# pcb-inductive-sensor.net
KiCad netlist of a schematic drawn in EAGLE
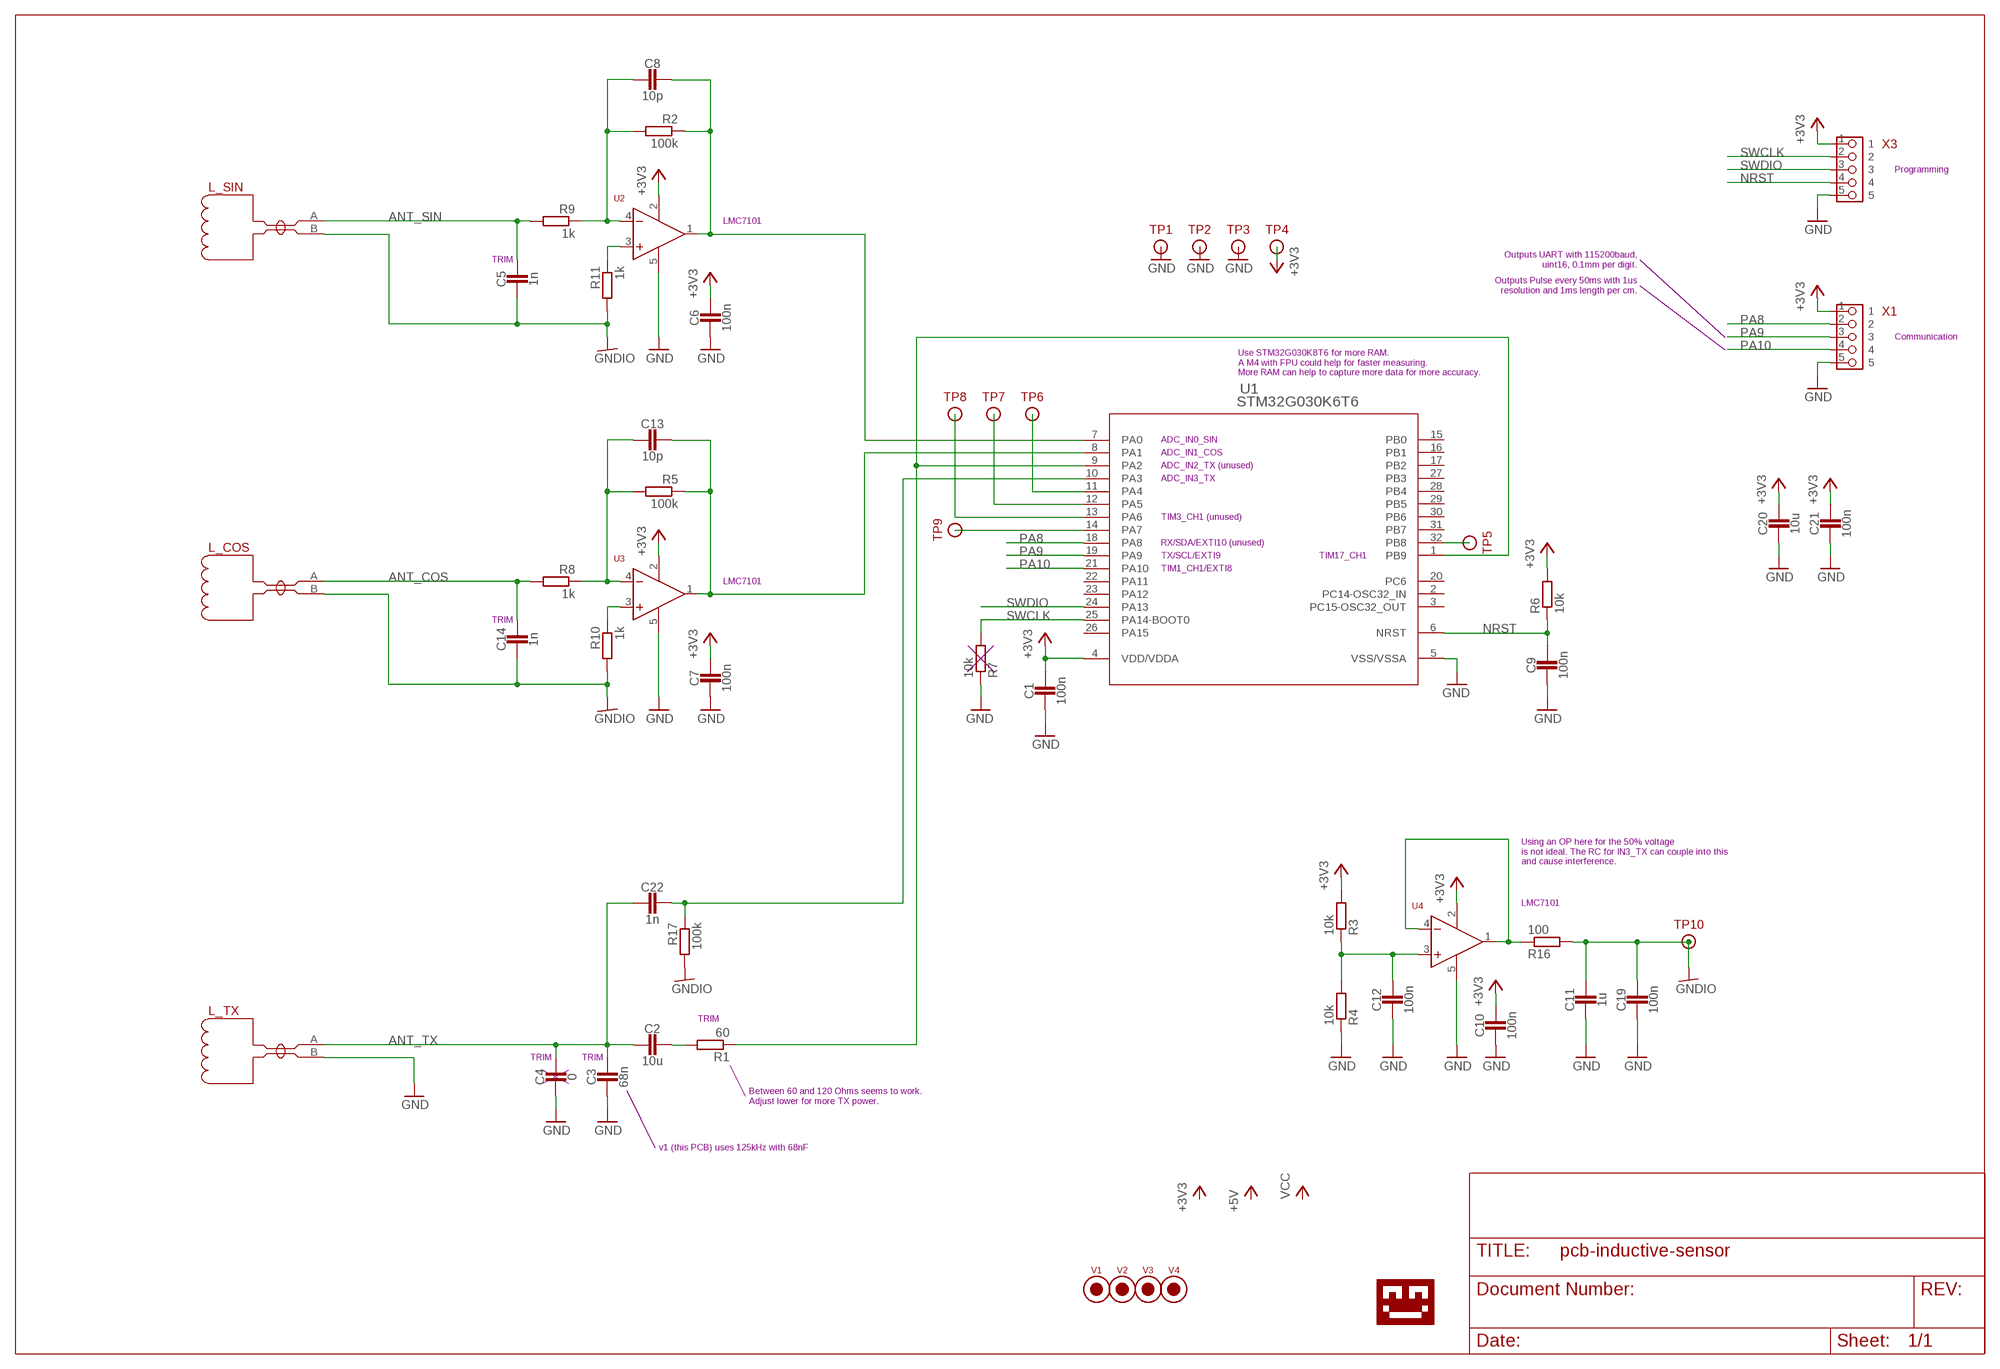
[diagram p0: schematic, sheet 1]

(export (version "E")
  (design (tool "Eeschema 10.0.6"))
  (components
    (comp (ref "C1")
      (value "100n")
      (footprint "eagle-import:0603_CAP")
      (libsource (lib "eagle-import") (part "CAPACITOR0603_CAP"))
    )
    (comp (ref "C2")
      (value "10u")
      (footprint "eagle-import:0805_CAP")
      (libsource (lib "eagle-import") (part "CAPACITOR0805_CAP"))
    )
    (comp (ref "C3")
      (value "68n")
      (footprint "eagle-import:0603_CAP")
      (libsource (lib "eagle-import") (part "CAPACITOR0603_CAP"))
    )
    (comp (ref "C4")
      (value "0")
      (footprint "eagle-import:0603_CAP")
      (libsource (lib "eagle-import") (part "CAPACITOR0603_CAP"))
    )
    (comp (ref "C5")
      (value "1n")
      (footprint "eagle-import:0603_CAP")
      (libsource (lib "eagle-import") (part "CAPACITOR0603_CAP"))
    )
    (comp (ref "C6")
      (value "100n")
      (footprint "eagle-import:0603_CAP")
      (libsource (lib "eagle-import") (part "CAPACITOR0603_CAP"))
    )
    (comp (ref "C7")
      (value "100n")
      (footprint "eagle-import:0603_CAP")
      (libsource (lib "eagle-import") (part "CAPACITOR0603_CAP"))
    )
    (comp (ref "C8")
      (value "10p")
      (footprint "eagle-import:0603_CAP")
      (libsource (lib "eagle-import") (part "CAPACITOR0603_CAP"))
    )
    (comp (ref "C9")
      (value "100n")
      (footprint "eagle-import:0603_CAP")
      (libsource (lib "eagle-import") (part "CAPACITOR0603_CAP"))
    )
    (comp (ref "C10")
      (value "100n")
      (footprint "eagle-import:0603_CAP")
      (libsource (lib "eagle-import") (part "CAPACITOR0603_CAP"))
    )
    (comp (ref "C11")
      (value "1u")
      (footprint "eagle-import:0603_CAP")
      (libsource (lib "eagle-import") (part "CAPACITOR0603_CAP"))
    )
    (comp (ref "C12")
      (value "100n")
      (footprint "eagle-import:0603_CAP")
      (libsource (lib "eagle-import") (part "CAPACITOR0603_CAP"))
    )
    (comp (ref "C13")
      (value "10p")
      (footprint "eagle-import:0603_CAP")
      (libsource (lib "eagle-import") (part "CAPACITOR0603_CAP"))
    )
    (comp (ref "C14")
      (value "1n")
      (footprint "eagle-import:0603_CAP")
      (libsource (lib "eagle-import") (part "CAPACITOR0603_CAP"))
    )
    (comp (ref "C19")
      (value "100n")
      (footprint "eagle-import:0603_CAP")
      (libsource (lib "eagle-import") (part "CAPACITOR0603_CAP"))
    )
    (comp (ref "C20")
      (value "10u")
      (footprint "eagle-import:0805_CAP")
      (libsource (lib "eagle-import") (part "CAPACITOR0805_CAP"))
    )
    (comp (ref "C21")
      (value "100n")
      (footprint "eagle-import:0603_CAP")
      (libsource (lib "eagle-import") (part "CAPACITOR0603_CAP"))
    )
    (comp (ref "C22")
      (value "1n")
      (footprint "eagle-import:0603_CAP")
      (libsource (lib "eagle-import") (part "CAPACITOR0603_CAP"))
    )
    (comp (ref "L_COS")
      (value "INDUCTION_SENSOR")
      (footprint "eagle-import:INDUCTIVE_SENSOR_NET_TIE")
      (libsource (lib "eagle-import") (part "INDUCTION_SENSOR"))
    )
    (comp (ref "L_SIN")
      (value "INDUCTION_SENSOR")
      (footprint "eagle-import:INDUCTIVE_SENSOR_NET_TIE")
      (libsource (lib "eagle-import") (part "INDUCTION_SENSOR"))
    )
    (comp (ref "L_TX")
      (value "INDUCTION_SENSOR")
      (footprint "eagle-import:INDUCTIVE_SENSOR_NET_TIE")
      (libsource (lib "eagle-import") (part "INDUCTION_SENSOR"))
    )
    (comp (ref "R1")
      (value "60")
      (footprint "eagle-import:0805_RES")
      (libsource (lib "eagle-import") (part "RESISTOR0805_RES"))
    )
    (comp (ref "R2")
      (value "100k")
      (footprint "eagle-import:0603-RES")
      (libsource (lib "eagle-import") (part "RESISTOR0603_RES"))
    )
    (comp (ref "R3")
      (value "10k")
      (footprint "eagle-import:0603-RES")
      (libsource (lib "eagle-import") (part "RESISTOR0603_RES"))
    )
    (comp (ref "R4")
      (value "10k")
      (footprint "eagle-import:0603-RES")
      (libsource (lib "eagle-import") (part "RESISTOR0603_RES"))
    )
    (comp (ref "R5")
      (value "100k")
      (footprint "eagle-import:0603-RES")
      (libsource (lib "eagle-import") (part "RESISTOR0603_RES"))
    )
    (comp (ref "R6")
      (value "10k")
      (footprint "eagle-import:0603-RES")
      (libsource (lib "eagle-import") (part "RESISTOR0603_RES"))
    )
    (comp (ref "R7")
      (value "10k")
      (footprint "eagle-import:0603-RES")
      (libsource (lib "eagle-import") (part "RESISTOR0603_RES"))
    )
    (comp (ref "R8")
      (value "1k")
      (footprint "eagle-import:0603-RES")
      (libsource (lib "eagle-import") (part "RESISTOR0603_RES"))
    )
    (comp (ref "R9")
      (value "1k")
      (footprint "eagle-import:0603-RES")
      (libsource (lib "eagle-import") (part "RESISTOR0603_RES"))
    )
    (comp (ref "R10")
      (value "1k")
      (footprint "eagle-import:0603-RES")
      (libsource (lib "eagle-import") (part "RESISTOR0603_RES"))
    )
    (comp (ref "R11")
      (value "1k")
      (footprint "eagle-import:0603-RES")
      (libsource (lib "eagle-import") (part "RESISTOR0603_RES"))
    )
    (comp (ref "R16")
      (value "100")
      (footprint "eagle-import:0603-RES")
      (libsource (lib "eagle-import") (part "RESISTOR0603_RES"))
    )
    (comp (ref "R17")
      (value "100k")
      (footprint "eagle-import:0603-RES")
      (libsource (lib "eagle-import") (part "RESISTOR0603_RES"))
    )
    (comp (ref "TP1")
      (value "TESTPIN")
      (footprint "eagle-import:PIN-SMD-1X1-TEST_1M5")
      (libsource (lib "eagle-import") (part "TESTPIN"))
    )
    (comp (ref "TP2")
      (value "TESTPIN")
      (footprint "eagle-import:PIN-SMD-1X1-TEST_1M5")
      (libsource (lib "eagle-import") (part "TESTPIN"))
    )
    (comp (ref "TP3")
      (value "TESTPIN")
      (footprint "eagle-import:PIN-SMD-1X1-TEST_1M5")
      (libsource (lib "eagle-import") (part "TESTPIN"))
    )
    (comp (ref "TP4")
      (value "TESTPIN")
      (footprint "eagle-import:PIN-SMD-1X1-TEST_1M5")
      (libsource (lib "eagle-import") (part "TESTPIN"))
    )
    (comp (ref "TP5")
      (value "TESTPIN")
      (footprint "eagle-import:PIN-SMD-1X1-TEST_1M5")
      (libsource (lib "eagle-import") (part "TESTPIN"))
    )
    (comp (ref "TP6")
      (value "TESTPIN")
      (footprint "eagle-import:PIN-SMD-1X1-TEST_1M5")
      (libsource (lib "eagle-import") (part "TESTPIN"))
    )
    (comp (ref "TP7")
      (value "TESTPIN")
      (footprint "eagle-import:PIN-SMD-1X1-TEST_1M5")
      (libsource (lib "eagle-import") (part "TESTPIN"))
    )
    (comp (ref "TP8")
      (value "TESTPIN")
      (footprint "eagle-import:PIN-SMD-1X1-TEST_1M5")
      (libsource (lib "eagle-import") (part "TESTPIN"))
    )
    (comp (ref "TP9")
      (value "TESTPIN")
      (footprint "eagle-import:PIN-SMD-1X1-TEST_1M5")
      (libsource (lib "eagle-import") (part "TESTPIN"))
    )
    (comp (ref "TP10")
      (value "TESTPIN")
      (footprint "eagle-import:PIN-SMD-1X1-TEST_1M5")
      (libsource (lib "eagle-import") (part "TESTPIN"))
    )
    (comp (ref "U$1")
      (value "LOGO-TOBENG-1MM-FINISH")
      (footprint "eagle-import:TOBENG-1MM-FINISH")
      (libsource (lib "eagle-import") (part "LOGO-TOBENG-1MM-FINISH"))
    )
    (comp (ref "U1")
      (value "STM32G030K6T6")
      (footprint "eagle-import:LQFP-32")
      (fields (field (name "COPYRIGHT") "Copyright (C) 2018 Accelerated Designs. All rights reserved"))
      (libsource (lib "eagle-import") (part "STM32G030K6T6"))
    )
    (comp (ref "U2")
      (value "OPAMP-LMC7101")
      (footprint "eagle-import:SOT-23-5")
      (libsource (lib "eagle-import") (part "OPAMP-LMC7101"))
    )
    (comp (ref "U3")
      (value "OPAMP-LMC7101")
      (footprint "eagle-import:SOT-23-5")
      (libsource (lib "eagle-import") (part "OPAMP-LMC7101"))
    )
    (comp (ref "U4")
      (value "OPAMP-LMC7101")
      (footprint "eagle-import:SOT-23-5")
      (libsource (lib "eagle-import") (part "OPAMP-LMC7101"))
    )
    (comp (ref "V1")
      (value "FIDUCIAL2MM")
      (footprint "eagle-import:FIDUCIAL_2MM")
      (libsource (lib "eagle-import") (part "FIDUCIAL2MM"))
    )
    (comp (ref "V2")
      (value "FIDUCIAL2MM")
      (footprint "eagle-import:FIDUCIAL_2MM")
      (libsource (lib "eagle-import") (part "FIDUCIAL2MM"))
    )
    (comp (ref "V3")
      (value "FIDUCIAL2MM")
      (footprint "eagle-import:FIDUCIAL_2MM")
      (libsource (lib "eagle-import") (part "FIDUCIAL2MM"))
    )
    (comp (ref "V4")
      (value "FIDUCIAL2MM")
      (footprint "eagle-import:FIDUCIAL_2MM")
      (libsource (lib "eagle-import") (part "FIDUCIAL2MM"))
    )
    (comp (ref "X1")
      (value "PIN_5X1HD")
      (footprint "eagle-import:PIN_5X1_HD")
      (libsource (lib "eagle-import") (part "PIN_5X1HD"))
    )
    (comp (ref "X3")
      (value "PIN_5X1HD")
      (footprint "eagle-import:PIN_5X1_HD")
      (libsource (lib "eagle-import") (part "PIN_5X1HD"))
    )
  )
  (nets
    (net (code "1") (name "+3V3") (class "Default")
      (node (ref "C1") (pin "1") (pinfunction "1_1") (pintype "bidirectional"))
      (node (ref "C10") (pin "1") (pinfunction "1_1") (pintype "bidirectional"))
      (node (ref "C20") (pin "P$1") (pinfunction "1_P$1") (pintype "bidirectional"))
      (node (ref "C21") (pin "1") (pinfunction "1_1") (pintype "bidirectional"))
      (node (ref "C6") (pin "1") (pinfunction "1_1") (pintype "bidirectional"))
      (node (ref "C7") (pin "1") (pinfunction "1_1") (pintype "bidirectional"))
      (node (ref "R3") (pin "2") (pinfunction "2_2") (pintype "passive"))
      (node (ref "R6") (pin "2") (pinfunction "2_2") (pintype "passive"))
      (node (ref "TP4") (pin "1") (pinfunction "1_1") (pintype "bidirectional"))
      (node (ref "U1") (pin "4") (pinfunction "VDD/VDDA_4") (pintype "power_in"))
      (node (ref "U2") (pin "2") (pinfunction "VCC_2") (pintype "bidirectional"))
      (node (ref "U3") (pin "2") (pinfunction "VCC_2") (pintype "bidirectional"))
      (node (ref "U4") (pin "2") (pinfunction "VCC_2") (pintype "bidirectional"))
      (node (ref "X1") (pin "1") (pinfunction "1_1") (pintype "bidirectional"))
      (node (ref "X3") (pin "1") (pinfunction "1_1") (pintype "bidirectional"))
    )
    (net (code "3") (name "/ANT_COS") (class "Default")
      (node (ref "C14") (pin "1") (pinfunction "1_1") (pintype "bidirectional"))
      (node (ref "L_COS") (pin "A") (pinfunction "A_A") (pintype "bidirectional"))
      (node (ref "R8") (pin "2") (pinfunction "2_2") (pintype "passive"))
    )
    (net (code "4") (name "/ANT_SIN") (class "Default")
      (node (ref "C5") (pin "1") (pinfunction "1_1") (pintype "bidirectional"))
      (node (ref "L_SIN") (pin "A") (pinfunction "A_A") (pintype "bidirectional"))
      (node (ref "R9") (pin "2") (pinfunction "2_2") (pintype "passive"))
    )
    (net (code "5") (name "/ANT_TX") (class "Default")
      (node (ref "C2") (pin "P$2") (pinfunction "2_P$2") (pintype "bidirectional"))
      (node (ref "C22") (pin "2") (pinfunction "2_2") (pintype "bidirectional"))
      (node (ref "C3") (pin "1") (pinfunction "1_1") (pintype "bidirectional"))
      (node (ref "C4") (pin "1") (pinfunction "1_1") (pintype "bidirectional"))
      (node (ref "L_TX") (pin "A") (pinfunction "A_A") (pintype "bidirectional"))
    )
    (net (code "6") (name "/NRST") (class "Default")
      (node (ref "C9") (pin "1") (pinfunction "1_1") (pintype "bidirectional"))
      (node (ref "R6") (pin "1") (pinfunction "1_1") (pintype "passive"))
      (node (ref "U1") (pin "6") (pinfunction "NRST_6") (pintype "bidirectional"))
      (node (ref "X3") (pin "4") (pinfunction "4_4") (pintype "bidirectional"))
    )
    (net (code "7") (name "/PA8") (class "Default")
      (node (ref "U1") (pin "18") (pinfunction "PA8_18") (pintype "bidirectional"))
      (node (ref "X1") (pin "2") (pinfunction "2_2") (pintype "bidirectional"))
    )
    (net (code "8") (name "/PA9") (class "Default")
      (node (ref "U1") (pin "19") (pinfunction "PA9_19") (pintype "bidirectional"))
      (node (ref "X1") (pin "3") (pinfunction "3_3") (pintype "bidirectional"))
    )
    (net (code "9") (name "/PA10") (class "Default")
      (node (ref "U1") (pin "21") (pinfunction "PA10_21") (pintype "bidirectional"))
      (node (ref "X1") (pin "4") (pinfunction "4_4") (pintype "bidirectional"))
    )
    (net (code "10") (name "/SWCLK") (class "Default")
      (node (ref "R7") (pin "2") (pinfunction "2_2") (pintype "passive"))
      (node (ref "U1") (pin "25") (pinfunction "PA14-BOOT0_25") (pintype "bidirectional"))
      (node (ref "X3") (pin "2") (pinfunction "2_2") (pintype "bidirectional"))
    )
    (net (code "11") (name "/SWDIO") (class "Default")
      (node (ref "U1") (pin "24") (pinfunction "PA13_24") (pintype "bidirectional"))
      (node (ref "X3") (pin "3") (pinfunction "3_3") (pintype "bidirectional"))
    )
    (net (code "12") (name "GND") (class "Default")
      (node (ref "C1") (pin "2") (pinfunction "2_2") (pintype "bidirectional"))
      (node (ref "C10") (pin "2") (pinfunction "2_2") (pintype "bidirectional"))
      (node (ref "C11") (pin "2") (pinfunction "2_2") (pintype "bidirectional"))
      (node (ref "C12") (pin "2") (pinfunction "2_2") (pintype "bidirectional"))
      (node (ref "C19") (pin "2") (pinfunction "2_2") (pintype "bidirectional"))
      (node (ref "C20") (pin "P$2") (pinfunction "2_P$2") (pintype "bidirectional"))
      (node (ref "C21") (pin "2") (pinfunction "2_2") (pintype "bidirectional"))
      (node (ref "C3") (pin "2") (pinfunction "2_2") (pintype "bidirectional"))
      (node (ref "C4") (pin "2") (pinfunction "2_2") (pintype "bidirectional"))
      (node (ref "C6") (pin "2") (pinfunction "2_2") (pintype "bidirectional"))
      (node (ref "C7") (pin "2") (pinfunction "2_2") (pintype "bidirectional"))
      (node (ref "C9") (pin "2") (pinfunction "2_2") (pintype "bidirectional"))
      (node (ref "L_TX") (pin "B") (pinfunction "B_B") (pintype "bidirectional"))
      (node (ref "R4") (pin "1") (pinfunction "1_1") (pintype "passive"))
      (node (ref "R7") (pin "1") (pinfunction "1_1") (pintype "passive"))
      (node (ref "TP1") (pin "1") (pinfunction "1_1") (pintype "bidirectional"))
      (node (ref "TP2") (pin "1") (pinfunction "1_1") (pintype "bidirectional"))
      (node (ref "TP3") (pin "1") (pinfunction "1_1") (pintype "bidirectional"))
      (node (ref "U1") (pin "5") (pinfunction "VSS/VSSA_5") (pintype "power_in"))
      (node (ref "U2") (pin "5") (pinfunction "GND_5") (pintype "bidirectional"))
      (node (ref "U3") (pin "5") (pinfunction "GND_5") (pintype "bidirectional"))
      (node (ref "U4") (pin "5") (pinfunction "GND_5") (pintype "bidirectional"))
      (node (ref "X1") (pin "5") (pinfunction "5_5") (pintype "bidirectional"))
      (node (ref "X3") (pin "5") (pinfunction "5_5") (pintype "bidirectional"))
    )
    (net (code "13") (name "GNDIO") (class "Default")
      (node (ref "C11") (pin "1") (pinfunction "1_1") (pintype "bidirectional"))
      (node (ref "C14") (pin "2") (pinfunction "2_2") (pintype "bidirectional"))
      (node (ref "C19") (pin "1") (pinfunction "1_1") (pintype "bidirectional"))
      (node (ref "C5") (pin "2") (pinfunction "2_2") (pintype "bidirectional"))
      (node (ref "L_COS") (pin "B") (pinfunction "B_B") (pintype "bidirectional"))
      (node (ref "L_SIN") (pin "B") (pinfunction "B_B") (pintype "bidirectional"))
      (node (ref "R10") (pin "2") (pinfunction "2_2") (pintype "passive"))
      (node (ref "R11") (pin "2") (pinfunction "2_2") (pintype "passive"))
      (node (ref "R16") (pin "2") (pinfunction "2_2") (pintype "passive"))
      (node (ref "R17") (pin "2") (pinfunction "2_2") (pintype "passive"))
      (node (ref "TP10") (pin "1") (pinfunction "1_1") (pintype "bidirectional"))
    )
    (net (code "14") (name "Net-(C2-1)") (class "Default")
      (node (ref "C2") (pin "P$1") (pinfunction "1_P$1") (pintype "bidirectional"))
      (node (ref "R1") (pin "2") (pinfunction "2_2") (pintype "passive"))
    )
    (net (code "15") (name "Net-(U1-PA0)") (class "Default")
      (node (ref "C8") (pin "1") (pinfunction "1_1") (pintype "bidirectional"))
      (node (ref "R2") (pin "1") (pinfunction "1_1") (pintype "passive"))
      (node (ref "U1") (pin "7") (pinfunction "PA0_7") (pintype "bidirectional"))
      (node (ref "U2") (pin "1") (pinfunction "OUT_1") (pintype "bidirectional"))
    )
    (net (code "16") (name "Net-(U1-PA1)") (class "Default")
      (node (ref "C13") (pin "1") (pinfunction "1_1") (pintype "bidirectional"))
      (node (ref "R5") (pin "1") (pinfunction "1_1") (pintype "passive"))
      (node (ref "U1") (pin "8") (pinfunction "PA1_8") (pintype "bidirectional"))
      (node (ref "U3") (pin "1") (pinfunction "OUT_1") (pintype "bidirectional"))
    )
    (net (code "17") (name "Net-(U1-PA2)") (class "Default")
      (node (ref "R1") (pin "1") (pinfunction "1_1") (pintype "passive"))
      (node (ref "U1") (pin "1") (pinfunction "PB9_1") (pintype "bidirectional"))
      (node (ref "U1") (pin "9") (pinfunction "PA2_9") (pintype "bidirectional"))
    )
    (net (code "18") (name "Net-(U1-PA3)") (class "Default")
      (node (ref "C22") (pin "1") (pinfunction "1_1") (pintype "bidirectional"))
      (node (ref "R17") (pin "1") (pinfunction "1_1") (pintype "passive"))
      (node (ref "U1") (pin "10") (pinfunction "PA3_10") (pintype "bidirectional"))
    )
    (net (code "19") (name "Net-(U1-PA4)") (class "Default")
      (node (ref "TP6") (pin "1") (pinfunction "1_1") (pintype "bidirectional"))
      (node (ref "U1") (pin "11") (pinfunction "PA4_11") (pintype "bidirectional"))
    )
    (net (code "20") (name "Net-(U1-PA5)") (class "Default")
      (node (ref "TP7") (pin "1") (pinfunction "1_1") (pintype "bidirectional"))
      (node (ref "U1") (pin "12") (pinfunction "PA5_12") (pintype "bidirectional"))
    )
    (net (code "21") (name "Net-(U1-PA6)") (class "Default")
      (node (ref "TP8") (pin "1") (pinfunction "1_1") (pintype "bidirectional"))
      (node (ref "U1") (pin "13") (pinfunction "PA6_13") (pintype "bidirectional"))
    )
    (net (code "22") (name "Net-(U1-PA7)") (class "Default")
      (node (ref "TP9") (pin "1") (pinfunction "1_1") (pintype "bidirectional"))
      (node (ref "U1") (pin "14") (pinfunction "PA7_14") (pintype "bidirectional"))
    )
    (net (code "23") (name "Net-(U1-PB8)") (class "Default")
      (node (ref "TP5") (pin "1") (pinfunction "1_1") (pintype "bidirectional"))
      (node (ref "U1") (pin "32") (pinfunction "PB8_32") (pintype "bidirectional"))
    )
    (net (code "24") (name "Net-(U2-+)") (class "Default")
      (node (ref "R11") (pin "1") (pinfunction "1_1") (pintype "passive"))
      (node (ref "U2") (pin "3") (pinfunction "+_3") (pintype "bidirectional"))
    )
    (net (code "25") (name "Net-(U2--)") (class "Default")
      (node (ref "C8") (pin "2") (pinfunction "2_2") (pintype "bidirectional"))
      (node (ref "R2") (pin "2") (pinfunction "2_2") (pintype "passive"))
      (node (ref "R9") (pin "1") (pinfunction "1_1") (pintype "passive"))
      (node (ref "U2") (pin "4") (pinfunction "-_4") (pintype "bidirectional"))
    )
    (net (code "26") (name "Net-(U3-+)") (class "Default")
      (node (ref "R10") (pin "1") (pinfunction "1_1") (pintype "passive"))
      (node (ref "U3") (pin "3") (pinfunction "+_3") (pintype "bidirectional"))
    )
    (net (code "27") (name "Net-(U3--)") (class "Default")
      (node (ref "C13") (pin "2") (pinfunction "2_2") (pintype "bidirectional"))
      (node (ref "R5") (pin "2") (pinfunction "2_2") (pintype "passive"))
      (node (ref "R8") (pin "1") (pinfunction "1_1") (pintype "passive"))
      (node (ref "U3") (pin "4") (pinfunction "-_4") (pintype "bidirectional"))
    )
    (net (code "28") (name "Net-(U4-+)") (class "Default")
      (node (ref "C12") (pin "1") (pinfunction "1_1") (pintype "bidirectional"))
      (node (ref "R3") (pin "1") (pinfunction "1_1") (pintype "passive"))
      (node (ref "R4") (pin "2") (pinfunction "2_2") (pintype "passive"))
      (node (ref "U4") (pin "3") (pinfunction "+_3") (pintype "bidirectional"))
    )
    (net (code "29") (name "Net-(U4--)") (class "Default")
      (node (ref "R16") (pin "1") (pinfunction "1_1") (pintype "passive"))
      (node (ref "U4") (pin "1") (pinfunction "OUT_1") (pintype "bidirectional"))
      (node (ref "U4") (pin "4") (pinfunction "-_4") (pintype "bidirectional"))
    )
    (net (code "31") (name "unconnected-(U1-PA11-Pad22)") (class "Default")
      (node (ref "U1") (pin "22") (pinfunction "PA11_22") (pintype "bidirectional"))
    )
    (net (code "32") (name "unconnected-(U1-PA12-Pad23)") (class "Default")
      (node (ref "U1") (pin "23") (pinfunction "PA12_23") (pintype "bidirectional"))
    )
    (net (code "33") (name "unconnected-(U1-PA15-Pad26)") (class "Default")
      (node (ref "U1") (pin "26") (pinfunction "PA15_26") (pintype "bidirectional"))
    )
    (net (code "34") (name "unconnected-(U1-PB0-Pad15)") (class "Default")
      (node (ref "U1") (pin "15") (pinfunction "PB0_15") (pintype "bidirectional"))
    )
    (net (code "35") (name "unconnected-(U1-PB1-Pad16)") (class "Default")
      (node (ref "U1") (pin "16") (pinfunction "PB1_16") (pintype "bidirectional"))
    )
    (net (code "36") (name "unconnected-(U1-PB2-Pad17)") (class "Default")
      (node (ref "U1") (pin "17") (pinfunction "PB2_17") (pintype "bidirectional"))
    )
    (net (code "37") (name "unconnected-(U1-PB3-Pad27)") (class "Default")
      (node (ref "U1") (pin "27") (pinfunction "PB3_27") (pintype "bidirectional"))
    )
    (net (code "38") (name "unconnected-(U1-PB4-Pad28)") (class "Default")
      (node (ref "U1") (pin "28") (pinfunction "PB4_28") (pintype "bidirectional"))
    )
    (net (code "39") (name "unconnected-(U1-PB5-Pad29)") (class "Default")
      (node (ref "U1") (pin "29") (pinfunction "PB5_29") (pintype "bidirectional"))
    )
    (net (code "40") (name "unconnected-(U1-PB6-Pad30)") (class "Default")
      (node (ref "U1") (pin "30") (pinfunction "PB6_30") (pintype "bidirectional"))
    )
    (net (code "41") (name "unconnected-(U1-PB7-Pad31)") (class "Default")
      (node (ref "U1") (pin "31") (pinfunction "PB7_31") (pintype "bidirectional"))
    )
    (net (code "42") (name "unconnected-(U1-PC6-Pad20)") (class "Default")
      (node (ref "U1") (pin "20") (pinfunction "PC6_20") (pintype "bidirectional"))
    )
    (net (code "43") (name "unconnected-(U1-PC14-OSC32_IN-Pad2)") (class "Default")
      (node (ref "U1") (pin "2") (pinfunction "PC14-OSC32_IN_2") (pintype "bidirectional"))
    )
    (net (code "44") (name "unconnected-(U1-PC15-OSC32_OUT-Pad3)") (class "Default")
      (node (ref "U1") (pin "3") (pinfunction "PC15-OSC32_OUT_3") (pintype "bidirectional"))
    )
  )
)
